# Mainboard.net
KiCad netlist of a schematic drawn in EAGLE
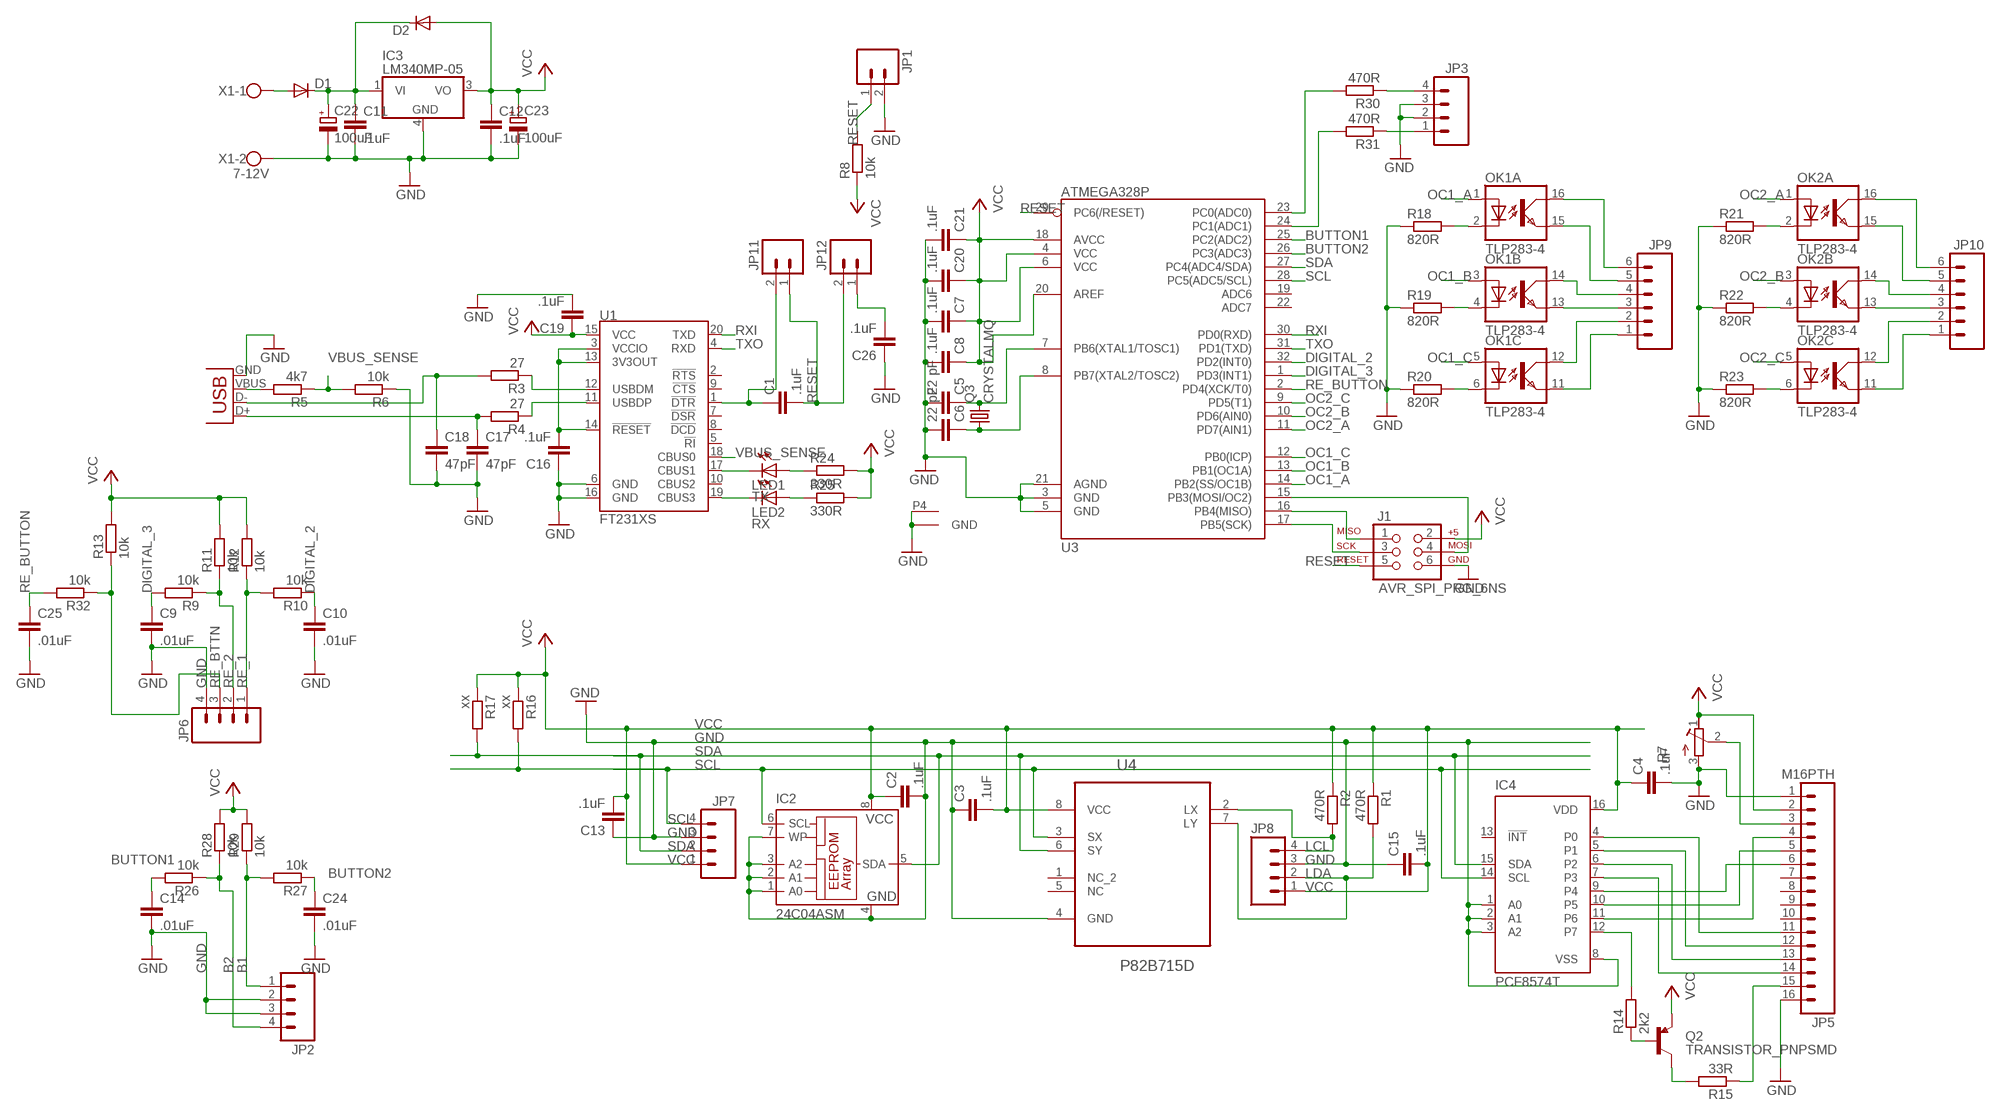
[diagram p0: schematic, sheet 1]

(export (version "E")
  (design (tool "Eeschema 10.0.6"))
  (components
    (comp (ref "C1")
      (value ".1uF")
      (footprint "eagle-import:C0805")
      (fields (field (name "MPN") "2222 370 21104"))
      (libsource (lib "eagle-import") (part "C-EUC0805"))
    )
    (comp (ref "C2")
      (value ".1uF")
      (footprint "eagle-import:C0805")
      (fields (field (name "MPN") "2222 370 21104"))
      (libsource (lib "eagle-import") (part "C-EUC0805"))
    )
    (comp (ref "C3")
      (value ".1uF")
      (footprint "eagle-import:C0805")
      (fields (field (name "MPN") "2222 370 21104"))
      (libsource (lib "eagle-import") (part "C-EUC0805"))
    )
    (comp (ref "C4")
      (value ".1uF")
      (footprint "eagle-import:C0805")
      (fields (field (name "MPN") "2222 370 21104"))
      (libsource (lib "eagle-import") (part "C-EUC0805"))
    )
    (comp (ref "C5")
      (value "22 pF")
      (footprint "eagle-import:C0805")
      (fields (field (name "MPN") "02013A220JAT2A"))
      (libsource (lib "eagle-import") (part "C-EUC0805"))
    )
    (comp (ref "C6")
      (value "22 pF")
      (footprint "eagle-import:C0805")
      (fields (field (name "MPN") "02013A220JAT2A"))
      (libsource (lib "eagle-import") (part "C-EUC0805"))
    )
    (comp (ref "C7")
      (value ".1uF")
      (footprint "eagle-import:C0805")
      (fields (field (name "MPN") "2222 370 21104"))
      (libsource (lib "eagle-import") (part "C-EUC0805"))
    )
    (comp (ref "C8")
      (value ".1uF")
      (footprint "eagle-import:C0805")
      (fields (field (name "MPN") "2222 370 21104"))
      (libsource (lib "eagle-import") (part "C-EUC0805"))
    )
    (comp (ref "C9")
      (value ".01uF")
      (footprint "eagle-import:C0805")
      (fields (field (name "MPN") "B32529C103K"))
      (libsource (lib "eagle-import") (part "C-EUC0805"))
    )
    (comp (ref "C10")
      (value ".01uF")
      (footprint "eagle-import:C0805")
      (fields (field (name "MPN") "B32529C103K"))
      (libsource (lib "eagle-import") (part "C-EUC0805"))
    )
    (comp (ref "C11")
      (value ".1uF")
      (footprint "eagle-import:C0805")
      (fields (field (name "MPN") "2222 370 21104"))
      (libsource (lib "eagle-import") (part "C-EUC0805"))
    )
    (comp (ref "C12")
      (value ".1uF")
      (footprint "eagle-import:C0805")
      (fields (field (name "MPN") "2222 370 21104"))
      (libsource (lib "eagle-import") (part "C-EUC0805"))
    )
    (comp (ref "C13")
      (value ".1uF")
      (footprint "eagle-import:C0805")
      (fields (field (name "MPN") "2222 370 21104"))
      (libsource (lib "eagle-import") (part "C-EUC0805"))
    )
    (comp (ref "C14")
      (value ".01uF")
      (footprint "eagle-import:C0805")
      (fields (field (name "MPN") "B32529C103K"))
      (libsource (lib "eagle-import") (part "C-EUC0805"))
    )
    (comp (ref "C15")
      (value ".1uF")
      (footprint "eagle-import:C0805")
      (fields (field (name "MPN") "2222 370 21104"))
      (libsource (lib "eagle-import") (part "C-EUC0805"))
    )
    (comp (ref "C16")
      (value ".1uF")
      (footprint "eagle-import:C0805")
      (fields (field (name "MPN") "2222 370 21104"))
      (libsource (lib "eagle-import") (part "C-EUC0805"))
    )
    (comp (ref "C17")
      (value "47pF")
      (footprint "eagle-import:C0805")
      (libsource (lib "eagle-import") (part "C-EUC0805"))
    )
    (comp (ref "C18")
      (value "47pF")
      (footprint "eagle-import:C0805")
      (libsource (lib "eagle-import") (part "C-EUC0805"))
    )
    (comp (ref "C19")
      (value ".1uF")
      (footprint "eagle-import:C0805")
      (fields (field (name "MPN") "2222 370 21104"))
      (libsource (lib "eagle-import") (part "C-EUC0805"))
    )
    (comp (ref "C20")
      (value ".1uF")
      (footprint "eagle-import:C0805")
      (fields (field (name "MPN") "2222 370 21104"))
      (libsource (lib "eagle-import") (part "C-EUC0805"))
    )
    (comp (ref "C21")
      (value ".1uF")
      (footprint "eagle-import:C0805")
      (fields (field (name "MPN") "2222 370 21104"))
      (libsource (lib "eagle-import") (part "C-EUC0805"))
    )
    (comp (ref "C22")
      (value "100uF")
      (footprint "eagle-import:PANASONIC_D")
      (libsource (lib "eagle-import") (part "CPOL-EUD"))
    )
    (comp (ref "C23")
      (value "100uF")
      (footprint "eagle-import:PANASONIC_D")
      (libsource (lib "eagle-import") (part "CPOL-EUD"))
    )
    (comp (ref "C24")
      (value ".01uF")
      (footprint "eagle-import:C0805")
      (fields (field (name "MPN") "B32529C103K"))
      (libsource (lib "eagle-import") (part "C-EUC0805"))
    )
    (comp (ref "C25")
      (value ".01uF")
      (footprint "eagle-import:C0805")
      (fields (field (name "MPN") "B32529C103K"))
      (libsource (lib "eagle-import") (part "C-EUC0805"))
    )
    (comp (ref "C26")
      (value ".1uF")
      (footprint "eagle-import:C0805")
      (fields (field (name "MPN") "2222 370 21104"))
      (libsource (lib "eagle-import") (part "C-EUC0805"))
    )
    (comp (ref "D1")
      (value "DIODE-MELF-MLL41")
      (footprint "eagle-import:MELF-MLL41")
      (libsource (lib "eagle-import") (part "DIODE-MELF-MLL41"))
    )
    (comp (ref "D2")
      (value "DIODE-MELF-MLL41")
      (footprint "eagle-import:MELF-MLL41")
      (libsource (lib "eagle-import") (part "DIODE-MELF-MLL41"))
    )
    (comp (ref "IC2")
      (value "24C04ASM")
      (footprint "eagle-import:SO-08M")
      (fields (field (name "MPN") "M24C04-WMN6P"))
      (libsource (lib "eagle-import") (part "24SMC04A"))
    )
    (comp (ref "IC3")
      (value "LM340MP-05")
      (footprint "eagle-import:SOT223")
      (libsource (lib "eagle-import") (part "LM340?-MP05"))
    )
    (comp (ref "IC4")
      (value "PCF8574T")
      (footprint "eagle-import:SO16W")
      (fields (field (name "MPN") "PCF8574T/3,512"))
      (libsource (lib "eagle-import") (part "PCF8574T"))
    )
    (comp (ref "J1")
      (value "AVR_SPI_PRG_6NS")
      (footprint "eagle-import:2X3-NS")
      (libsource (lib "eagle-import") (part "AVR_SPI_PRG_6NS"))
    )
    (comp (ref "JP1")
      (value "M02POLAR")
      (footprint "eagle-import:MOLEX-1X2")
      (libsource (lib "eagle-import") (part "M02POLAR"))
    )
    (comp (ref "JP2")
      (value "M04POLAR")
      (footprint "eagle-import:MOLEX-1X4")
      (libsource (lib "eagle-import") (part "M04POLAR"))
    )
    (comp (ref "JP3")
      (value "M04PTH")
      (footprint "eagle-import:1X04")
      (libsource (lib "eagle-import") (part "M04PTH"))
    )
    (comp (ref "JP4")
      (value "USB-B")
      (footprint "eagle-import:USB-B-PTH")
      (libsource (lib "eagle-import") (part "USBPTH"))
    )
    (comp (ref "JP5")
      (value "M16PTH")
      (footprint "eagle-import:1X16")
      (libsource (lib "eagle-import") (part "M16PTH"))
    )
    (comp (ref "JP6")
      (value "M04POLAR")
      (footprint "eagle-import:MOLEX-1X4")
      (libsource (lib "eagle-import") (part "M04POLAR"))
    )
    (comp (ref "JP7")
      (value "M04POLAR")
      (footprint "eagle-import:MOLEX-1X4")
      (libsource (lib "eagle-import") (part "M04POLAR"))
    )
    (comp (ref "JP8")
      (value "M04POLAR")
      (footprint "eagle-import:MOLEX-1X4")
      (libsource (lib "eagle-import") (part "M04POLAR"))
    )
    (comp (ref "JP9")
      (value "M06POLAR")
      (footprint "eagle-import:MOLEX-1X6")
      (libsource (lib "eagle-import") (part "M06POLAR"))
    )
    (comp (ref "JP10")
      (value "M06POLAR")
      (footprint "eagle-import:MOLEX-1X6")
      (libsource (lib "eagle-import") (part "M06POLAR"))
    )
    (comp (ref "JP11")
      (value "M02PTH")
      (footprint "eagle-import:1X02")
      (libsource (lib "eagle-import") (part "M02PTH"))
    )
    (comp (ref "JP12")
      (value "M02PTH")
      (footprint "eagle-import:1X02")
      (libsource (lib "eagle-import") (part "M02PTH"))
    )
    (comp (ref "LED1")
      (value "TX")
      (footprint "eagle-import:CHIPLED_0805")
      (libsource (lib "eagle-import") (part "LEDCHIPLED_0805"))
    )
    (comp (ref "LED2")
      (value "RX")
      (footprint "eagle-import:CHIPLED_0805")
      (libsource (lib "eagle-import") (part "LEDCHIPLED_0805"))
    )
    (comp (ref "OK1")
      (value "TLP283-4")
      (footprint "eagle-import:MINI-FLAT-16")
      (libsource (lib "eagle-import") (part "TLP283-4"))
    )
    (comp (ref "OK2")
      (value "TLP283-4")
      (footprint "eagle-import:MINI-FLAT-16")
      (libsource (lib "eagle-import") (part "TLP283-4"))
    )
    (comp (ref "Q2")
      (value "TRANSISTOR_PNPSMD")
      (footprint "eagle-import:SOT23-3")
      (libsource (lib "eagle-import") (part "TRANSISTOR_PNPSMD"))
    )
    (comp (ref "Q3")
      (value "CRYSTALMQ")
      (footprint "eagle-import:MQ")
      (libsource (lib "eagle-import") (part "CRYSTALMQ"))
    )
    (comp (ref "R1")
      (value "470R")
      (footprint "eagle-import:R0805")
      (libsource (lib "eagle-import") (part "R-EU_R0805"))
    )
    (comp (ref "R2")
      (value "470R")
      (footprint "eagle-import:R0805")
      (libsource (lib "eagle-import") (part "R-EU_R0805"))
    )
    (comp (ref "R3")
      (value "27")
      (footprint "eagle-import:R0805")
      (libsource (lib "eagle-import") (part "R-EU_R0805"))
    )
    (comp (ref "R4")
      (value "27")
      (footprint "eagle-import:R0805")
      (libsource (lib "eagle-import") (part "R-EU_R0805"))
    )
    (comp (ref "R5")
      (value "4k7")
      (footprint "eagle-import:R0805")
      (libsource (lib "eagle-import") (part "R-EU_R0805"))
    )
    (comp (ref "R6")
      (value "10k")
      (footprint "eagle-import:R0805")
      (fields (field (name "MF") "VISHAY/SPECTRO") (field (name "MPN") "043P103"))
      (libsource (lib "eagle-import") (part "R-EU_R0805"))
    )
    (comp (ref "R7")
      (value "R-TRIMM3314G")
      (footprint "eagle-import:RTRIM3314G")
      (libsource (lib "eagle-import") (part "R-TRIMM3314G"))
    )
    (comp (ref "R8")
      (value "10k")
      (footprint "eagle-import:R0805")
      (fields (field (name "MF") "VISHAY/SPECTRO") (field (name "MPN") "043P103"))
      (libsource (lib "eagle-import") (part "R-EU_R0805"))
    )
    (comp (ref "R9")
      (value "10k")
      (footprint "eagle-import:R0805")
      (fields (field (name "MF") "VISHAY/SPECTRO") (field (name "MPN") "043P103"))
      (libsource (lib "eagle-import") (part "R-EU_R0805"))
    )
    (comp (ref "R10")
      (value "10k")
      (footprint "eagle-import:R0805")
      (fields (field (name "MF") "VISHAY/SPECTRO") (field (name "MPN") "043P103"))
      (libsource (lib "eagle-import") (part "R-EU_R0805"))
    )
    (comp (ref "R11")
      (value "10k")
      (footprint "eagle-import:R0805")
      (fields (field (name "MF") "VISHAY/SPECTRO") (field (name "MPN") "043P103"))
      (libsource (lib "eagle-import") (part "R-EU_R0805"))
    )
    (comp (ref "R12")
      (value "10k")
      (footprint "eagle-import:R0805")
      (fields (field (name "MF") "VISHAY/SPECTRO") (field (name "MPN") "043P103"))
      (libsource (lib "eagle-import") (part "R-EU_R0805"))
    )
    (comp (ref "R13")
      (value "10k")
      (footprint "eagle-import:R0805")
      (fields (field (name "MF") "VISHAY/SPECTRO") (field (name "MPN") "043P103"))
      (libsource (lib "eagle-import") (part "R-EU_R0805"))
    )
    (comp (ref "R14")
      (value "2k2")
      (footprint "eagle-import:R0805")
      (fields (field (name "MF") "VISHAY/SPECTRO") (field (name "MPN") "043P103"))
      (libsource (lib "eagle-import") (part "R-EU_R0805"))
    )
    (comp (ref "R15")
      (value "33R")
      (footprint "eagle-import:R0805")
      (fields (field (name "MF") "VISHAY/SPECTRO") (field (name "MPN") "043P103"))
      (libsource (lib "eagle-import") (part "R-EU_R0805"))
    )
    (comp (ref "R16")
      (value "xx")
      (footprint "eagle-import:R0805")
      (libsource (lib "eagle-import") (part "R-EU_R0805"))
    )
    (comp (ref "R17")
      (value "xx")
      (footprint "eagle-import:R0805")
      (libsource (lib "eagle-import") (part "R-EU_R0805"))
    )
    (comp (ref "R18")
      (value "820R")
      (footprint "eagle-import:R0805")
      (libsource (lib "eagle-import") (part "R-EU_R0805"))
    )
    (comp (ref "R19")
      (value "820R")
      (footprint "eagle-import:R0805")
      (libsource (lib "eagle-import") (part "R-EU_R0805"))
    )
    (comp (ref "R20")
      (value "820R")
      (footprint "eagle-import:R0805")
      (libsource (lib "eagle-import") (part "R-EU_R0805"))
    )
    (comp (ref "R21")
      (value "820R")
      (footprint "eagle-import:R0805")
      (libsource (lib "eagle-import") (part "R-EU_R0805"))
    )
    (comp (ref "R22")
      (value "820R")
      (footprint "eagle-import:R0805")
      (libsource (lib "eagle-import") (part "R-EU_R0805"))
    )
    (comp (ref "R23")
      (value "820R")
      (footprint "eagle-import:R0805")
      (libsource (lib "eagle-import") (part "R-EU_R0805"))
    )
    (comp (ref "R24")
      (value "330R")
      (footprint "eagle-import:R0805")
      (libsource (lib "eagle-import") (part "R-EU_R0805"))
    )
    (comp (ref "R25")
      (value "330R")
      (footprint "eagle-import:R0805")
      (libsource (lib "eagle-import") (part "R-EU_R0805"))
    )
    (comp (ref "R26")
      (value "10k")
      (footprint "eagle-import:R0805")
      (fields (field (name "MF") "VISHAY/SPECTRO") (field (name "MPN") "043P103"))
      (libsource (lib "eagle-import") (part "R-EU_R0805"))
    )
    (comp (ref "R27")
      (value "10k")
      (footprint "eagle-import:R0805")
      (fields (field (name "MF") "VISHAY/SPECTRO") (field (name "MPN") "043P103"))
      (libsource (lib "eagle-import") (part "R-EU_R0805"))
    )
    (comp (ref "R28")
      (value "10k")
      (footprint "eagle-import:R0805")
      (fields (field (name "MF") "VISHAY/SPECTRO") (field (name "MPN") "043P103"))
      (libsource (lib "eagle-import") (part "R-EU_R0805"))
    )
    (comp (ref "R29")
      (value "10k")
      (footprint "eagle-import:R0805")
      (fields (field (name "MF") "VISHAY/SPECTRO") (field (name "MPN") "043P103"))
      (libsource (lib "eagle-import") (part "R-EU_R0805"))
    )
    (comp (ref "R30")
      (value "470R")
      (footprint "eagle-import:R0805")
      (fields (field (name "MF") "VISHAY/SPECTRO") (field (name "MPN") "043P103"))
      (libsource (lib "eagle-import") (part "R-EU_R0805"))
    )
    (comp (ref "R31")
      (value "470R")
      (footprint "eagle-import:R0805")
      (fields (field (name "MF") "VISHAY/SPECTRO") (field (name "MPN") "043P103"))
      (libsource (lib "eagle-import") (part "R-EU_R0805"))
    )
    (comp (ref "R32")
      (value "10k")
      (footprint "eagle-import:R0805")
      (fields (field (name "MF") "VISHAY/SPECTRO") (field (name "MPN") "043P103"))
      (libsource (lib "eagle-import") (part "R-EU_R0805"))
    )
    (comp (ref "U1")
      (value "FT231XS")
      (footprint "eagle-import:SSOP20_L")
      (libsource (lib "eagle-import") (part "FT231XS"))
    )
    (comp (ref "U3")
      (value "ATMEGA328P")
      (footprint "eagle-import:TQFP32-08")
      (libsource (lib "eagle-import") (part "ATMEGA328_SMT"))
    )
    (comp (ref "U4")
      (value "P82B715D")
      (footprint "eagle-import:SOIC127P600X175-8N")
      (libsource (lib "eagle-import") (part "P82B715D"))
    )
    (comp (ref "X1")
      (value "7-12V")
      (footprint "eagle-import:W237-102")
      (fields (field (name "MPN") "237-102") (field (name "OC_NEWARK") "unknown"))
      (libsource (lib "eagle-import") (part "W237-102"))
    )
  )
  (nets
    (net (code "1") (name "/B1") (class "Default")
      (node (ref "JP2") (pin "1") (pinfunction "1_1") (pintype "passive"))
      (node (ref "R27") (pin "2") (pinfunction "2_2") (pintype "passive"))
      (node (ref "R29") (pin "1") (pinfunction "1_1") (pintype "passive"))
    )
    (net (code "2") (name "/B2") (class "Default")
      (node (ref "JP2") (pin "4") (pinfunction "4_4") (pintype "passive"))
      (node (ref "R26") (pin "1") (pinfunction "1_1") (pintype "passive"))
      (node (ref "R28") (pin "1") (pinfunction "1_1") (pintype "passive"))
    )
    (net (code "3") (name "/BUTTON1") (class "Default")
      (node (ref "C14") (pin "1") (pinfunction "1_1") (pintype "passive"))
      (node (ref "R26") (pin "2") (pinfunction "2_2") (pintype "passive"))
      (node (ref "U3") (pin "25") (pinfunction "PC2(ADC2)_25") (pintype "bidirectional"))
    )
    (net (code "4") (name "/BUTTON2") (class "Default")
      (node (ref "C24") (pin "1") (pinfunction "1_1") (pintype "passive"))
      (node (ref "R27") (pin "1") (pinfunction "1_1") (pintype "passive"))
      (node (ref "U3") (pin "26") (pinfunction "PC3(ADC3)_26") (pintype "bidirectional"))
    )
    (net (code "5") (name "/DIGITAL_2") (class "Default")
      (node (ref "C10") (pin "1") (pinfunction "1_1") (pintype "passive"))
      (node (ref "R10") (pin "1") (pinfunction "1_1") (pintype "passive"))
      (node (ref "U3") (pin "32") (pinfunction "PD2(INT0)_32") (pintype "bidirectional"))
    )
    (net (code "6") (name "/DIGITAL_3") (class "Default")
      (node (ref "C9") (pin "1") (pinfunction "1_1") (pintype "passive"))
      (node (ref "R9") (pin "2") (pinfunction "2_2") (pintype "passive"))
      (node (ref "U3") (pin "1") (pinfunction "PD3(INT1)_1") (pintype "bidirectional"))
    )
    (net (code "7") (name "/LCL") (class "Default")
      (node (ref "JP8") (pin "4") (pinfunction "4_4") (pintype "passive"))
      (node (ref "R2") (pin "2") (pinfunction "2_2") (pintype "passive"))
      (node (ref "U4") (pin "2") (pinfunction "LX_2") (pintype "output"))
    )
    (net (code "8") (name "/LDA") (class "Default")
      (node (ref "JP8") (pin "2") (pinfunction "2_2") (pintype "passive"))
      (node (ref "R1") (pin "2") (pinfunction "2_2") (pintype "passive"))
      (node (ref "U4") (pin "7") (pinfunction "LY_7") (pintype "output"))
    )
    (net (code "9") (name "/OC1_A") (class "Default")
      (node (ref "OK1") (pin "1") (pinfunction "A_1") (pintype "passive"))
      (node (ref "U3") (pin "14") (pinfunction "PB2(SS/OC1B)_14") (pintype "bidirectional"))
    )
    (net (code "10") (name "/OC1_B") (class "Default")
      (node (ref "OK1") (pin "3") (pinfunction "A_3") (pintype "passive"))
      (node (ref "U3") (pin "13") (pinfunction "PB1(OC1A)_13") (pintype "bidirectional"))
    )
    (net (code "11") (name "/OC1_C") (class "Default")
      (node (ref "OK1") (pin "5") (pinfunction "A_5") (pintype "passive"))
      (node (ref "U3") (pin "12") (pinfunction "PB0(ICP)_12") (pintype "bidirectional"))
    )
    (net (code "12") (name "/OC2_A") (class "Default")
      (node (ref "OK2") (pin "1") (pinfunction "A_1") (pintype "passive"))
      (node (ref "U3") (pin "11") (pinfunction "PD7(AIN1)_11") (pintype "bidirectional"))
    )
    (net (code "13") (name "/OC2_B") (class "Default")
      (node (ref "OK2") (pin "3") (pinfunction "A_3") (pintype "passive"))
      (node (ref "U3") (pin "10") (pinfunction "PD6(AIN0)_10") (pintype "bidirectional"))
    )
    (net (code "14") (name "/OC2_C") (class "Default")
      (node (ref "OK2") (pin "5") (pinfunction "A_5") (pintype "passive"))
      (node (ref "U3") (pin "9") (pinfunction "PD5(T1)_9") (pintype "bidirectional"))
    )
    (net (code "15") (name "/RESET") (class "Default")
      (node (ref "C1") (pin "2") (pinfunction "2_2") (pintype "passive"))
      (node (ref "J1") (pin "5") (pinfunction "5_5") (pintype "passive"))
      (node (ref "JP1") (pin "1") (pinfunction "1_1") (pintype "passive"))
      (node (ref "JP11") (pin "1") (pinfunction "1_1") (pintype "passive"))
      (node (ref "JP12") (pin "2") (pinfunction "2_2") (pintype "passive"))
      (node (ref "R8") (pin "2") (pinfunction "2_2") (pintype "passive"))
      (node (ref "U3") (pin "29") (pinfunction "PC6(/RESET)_29") (pintype "bidirectional"))
    )
    (net (code "16") (name "/RE_1") (class "Default")
      (node (ref "JP6") (pin "1") (pinfunction "1_1") (pintype "passive"))
      (node (ref "R10") (pin "2") (pinfunction "2_2") (pintype "passive"))
      (node (ref "R12") (pin "1") (pinfunction "1_1") (pintype "passive"))
    )
    (net (code "17") (name "/RE_2") (class "Default")
      (node (ref "JP6") (pin "2") (pinfunction "2_2") (pintype "passive"))
      (node (ref "R11") (pin "1") (pinfunction "1_1") (pintype "passive"))
      (node (ref "R9") (pin "1") (pinfunction "1_1") (pintype "passive"))
    )
    (net (code "18") (name "/RE_BTTN") (class "Default")
      (node (ref "JP6") (pin "3") (pinfunction "3_3") (pintype "passive"))
      (node (ref "R13") (pin "1") (pinfunction "1_1") (pintype "passive"))
      (node (ref "R32") (pin "1") (pinfunction "1_1") (pintype "passive"))
    )
    (net (code "19") (name "/RE_BUTTON") (class "Default")
      (node (ref "C25") (pin "1") (pinfunction "1_1") (pintype "passive"))
      (node (ref "R32") (pin "2") (pinfunction "2_2") (pintype "passive"))
      (node (ref "U3") (pin "2") (pinfunction "PD4(XCK/T0)_2") (pintype "bidirectional"))
    )
    (net (code "20") (name "/RXI") (class "Default")
      (node (ref "U1") (pin "20") (pinfunction "TXD_20") (pintype "bidirectional"))
      (node (ref "U3") (pin "30") (pinfunction "PD0(RXD)_30") (pintype "bidirectional"))
    )
    (net (code "21") (name "/SCL") (class "Default")
      (node (ref "IC2") (pin "6") (pinfunction "SCL_6") (pintype "input"))
      (node (ref "IC4") (pin "14") (pinfunction "SCL_14") (pintype "input"))
      (node (ref "JP7") (pin "4") (pinfunction "4_4") (pintype "passive"))
      (node (ref "R16") (pin "2") (pinfunction "2_2") (pintype "passive"))
      (node (ref "U3") (pin "28") (pinfunction "PC5(ADC5/SCL)_28") (pintype "bidirectional"))
      (node (ref "U4") (pin "3") (pinfunction "SX_3") (pintype "input"))
    )
    (net (code "22") (name "/SDA") (class "Default")
      (node (ref "IC2") (pin "5") (pinfunction "SDA_5") (pintype "bidirectional"))
      (node (ref "IC4") (pin "15") (pinfunction "SDA_15") (pintype "bidirectional"))
      (node (ref "JP7") (pin "2") (pinfunction "2_2") (pintype "passive"))
      (node (ref "R17") (pin "2") (pinfunction "2_2") (pintype "passive"))
      (node (ref "U3") (pin "27") (pinfunction "PC4(ADC4/SDA)_27") (pintype "bidirectional"))
      (node (ref "U4") (pin "6") (pinfunction "SY_6") (pintype "input"))
    )
    (net (code "23") (name "/TXO") (class "Default")
      (node (ref "U1") (pin "4") (pinfunction "RXD_4") (pintype "bidirectional"))
      (node (ref "U3") (pin "31") (pinfunction "PD1(TXD)_31") (pintype "bidirectional"))
    )
    (net (code "24") (name "/VBUS_SENSE") (class "Default")
      (node (ref "R5") (pin "1") (pinfunction "1_1") (pintype "passive"))
      (node (ref "R6") (pin "2") (pinfunction "2_2") (pintype "passive"))
      (node (ref "U1") (pin "18") (pinfunction "CBUS0_18") (pintype "bidirectional"))
    )
    (net (code "25") (name "GND") (class "Default")
      (node (ref "C10") (pin "2") (pinfunction "2_2") (pintype "passive"))
      (node (ref "C11") (pin "2") (pinfunction "2_2") (pintype "passive"))
      (node (ref "C12") (pin "2") (pinfunction "2_2") (pintype "passive"))
      (node (ref "C13") (pin "1") (pinfunction "1_1") (pintype "passive"))
      (node (ref "C14") (pin "2") (pinfunction "2_2") (pintype "passive"))
      (node (ref "C15") (pin "1") (pinfunction "1_1") (pintype "passive"))
      (node (ref "C16") (pin "1") (pinfunction "1_1") (pintype "passive"))
      (node (ref "C17") (pin "2") (pinfunction "2_2") (pintype "passive"))
      (node (ref "C18") (pin "2") (pinfunction "2_2") (pintype "passive"))
      (node (ref "C19") (pin "2") (pinfunction "2_2") (pintype "passive"))
      (node (ref "C2") (pin "2") (pinfunction "2_2") (pintype "passive"))
      (node (ref "C20") (pin "2") (pinfunction "2_2") (pintype "passive"))
      (node (ref "C21") (pin "2") (pinfunction "2_2") (pintype "passive"))
      (node (ref "C22") (pin "-") (pinfunction "-_-") (pintype "passive"))
      (node (ref "C23") (pin "-") (pinfunction "-_-") (pintype "passive"))
      (node (ref "C24") (pin "2") (pinfunction "2_2") (pintype "passive"))
      (node (ref "C25") (pin "2") (pinfunction "2_2") (pintype "passive"))
      (node (ref "C26") (pin "1") (pinfunction "1_1") (pintype "passive"))
      (node (ref "C3") (pin "1") (pinfunction "1_1") (pintype "passive"))
      (node (ref "C4") (pin "2") (pinfunction "2_2") (pintype "passive"))
      (node (ref "C5") (pin "2") (pinfunction "2_2") (pintype "passive"))
      (node (ref "C6") (pin "2") (pinfunction "2_2") (pintype "passive"))
      (node (ref "C7") (pin "2") (pinfunction "2_2") (pintype "passive"))
      (node (ref "C8") (pin "2") (pinfunction "2_2") (pintype "passive"))
      (node (ref "C9") (pin "2") (pinfunction "2_2") (pintype "passive"))
      (node (ref "IC2") (pin "1") (pinfunction "A0_1") (pintype "input"))
      (node (ref "IC2") (pin "2") (pinfunction "A1_2") (pintype "input"))
      (node (ref "IC2") (pin "3") (pinfunction "A2_3") (pintype "input"))
      (node (ref "IC2") (pin "4") (pinfunction "GND_4") (pintype "power_in"))
      (node (ref "IC2") (pin "7") (pinfunction "WP_7") (pintype "input"))
      (node (ref "IC3") (pin "4") (pinfunction "GND_4") (pintype "passive"))
      (node (ref "IC4") (pin "1") (pinfunction "A0_1") (pintype "input"))
      (node (ref "IC4") (pin "2") (pinfunction "A1_2") (pintype "input"))
      (node (ref "IC4") (pin "3") (pinfunction "A2_3") (pintype "input"))
      (node (ref "IC4") (pin "8") (pinfunction "VSS_8") (pintype "power_in"))
      (node (ref "J1") (pin "6") (pinfunction "6_6") (pintype "passive"))
      (node (ref "JP1") (pin "2") (pinfunction "2_2") (pintype "passive"))
      (node (ref "JP2") (pin "2") (pinfunction "2_2") (pintype "passive"))
      (node (ref "JP2") (pin "3") (pinfunction "3_3") (pintype "passive"))
      (node (ref "JP3") (pin "2") (pinfunction "2_2") (pintype "passive"))
      (node (ref "JP3") (pin "3") (pinfunction "3_3") (pintype "passive"))
      (node (ref "JP4") (pin "GND") (pinfunction "GND_GND") (pintype "bidirectional"))
      (node (ref "JP5") (pin "1") (pinfunction "1_1") (pintype "passive"))
      (node (ref "JP5") (pin "16") (pinfunction "16_16") (pintype "passive"))
      (node (ref "JP6") (pin "4") (pinfunction "4_4") (pintype "passive"))
      (node (ref "JP7") (pin "3") (pinfunction "3_3") (pintype "passive"))
      (node (ref "JP8") (pin "3") (pinfunction "3_3") (pintype "passive"))
      (node (ref "Q3") (pin "P2") (pinfunction "GND_P2") (pintype "bidirectional"))
      (node (ref "Q3") (pin "P4") (pinfunction "GND1_P4") (pintype "bidirectional"))
      (node (ref "R18") (pin "1") (pinfunction "1_1") (pintype "passive"))
      (node (ref "R19") (pin "1") (pinfunction "1_1") (pintype "passive"))
      (node (ref "R20") (pin "1") (pinfunction "1_1") (pintype "passive"))
      (node (ref "R21") (pin "1") (pinfunction "1_1") (pintype "passive"))
      (node (ref "R22") (pin "1") (pinfunction "1_1") (pintype "passive"))
      (node (ref "R23") (pin "1") (pinfunction "1_1") (pintype "passive"))
      (node (ref "R6") (pin "1") (pinfunction "1_1") (pintype "passive"))
      (node (ref "R7") (pin "3") (pinfunction "A_3") (pintype "passive"))
      (node (ref "U1") (pin "16") (pinfunction "GND_16") (pintype "bidirectional"))
      (node (ref "U1") (pin "6") (pinfunction "GND_6") (pintype "bidirectional"))
      (node (ref "U3") (pin "21") (pinfunction "AGND_21") (pintype "bidirectional"))
      (node (ref "U3") (pin "3") (pinfunction "GND_3") (pintype "bidirectional"))
      (node (ref "U3") (pin "5") (pinfunction "GND_5") (pintype "bidirectional"))
      (node (ref "U4") (pin "4") (pinfunction "GND_4") (pintype "passive"))
      (node (ref "X1") (pin "2") (pinfunction "KL_2") (pintype "passive"))
    )
    (net (code "26") (name "Net-(C17-Pad1)") (class "Default")
      (node (ref "C17") (pin "1") (pinfunction "1_1") (pintype "passive"))
      (node (ref "JP4") (pin "D+") (pinfunction "D+_D+") (pintype "bidirectional"))
      (node (ref "R4") (pin "2") (pinfunction "2_2") (pintype "passive"))
    )
    (net (code "27") (name "Net-(C18-Pad1)") (class "Default")
      (node (ref "C18") (pin "1") (pinfunction "1_1") (pintype "passive"))
      (node (ref "JP4") (pin "D-") (pinfunction "D-_D-") (pintype "bidirectional"))
      (node (ref "R3") (pin "2") (pinfunction "2_2") (pintype "passive"))
    )
    (net (code "28") (name "Net-(C26-Pad2)") (class "Default")
      (node (ref "C26") (pin "2") (pinfunction "2_2") (pintype "passive"))
      (node (ref "JP12") (pin "1") (pinfunction "1_1") (pintype "passive"))
    )
    (net (code "29") (name "Net-(IC3-VI)") (class "Default")
      (node (ref "C11") (pin "1") (pinfunction "1_1") (pintype "passive"))
      (node (ref "C22") (pin "+") (pinfunction "+_+") (pintype "passive"))
      (node (ref "D1") (pin "C") (pinfunction "C_C") (pintype "passive"))
      (node (ref "D2") (pin "C") (pinfunction "C_C") (pintype "passive"))
      (node (ref "IC3") (pin "1") (pinfunction "VI_1") (pintype "input"))
    )
    (net (code "30") (name "Net-(IC4-P0)") (class "Default")
      (node (ref "IC4") (pin "4") (pinfunction "P0_4") (pintype "bidirectional"))
      (node (ref "JP5") (pin "11") (pinfunction "11_11") (pintype "passive"))
    )
    (net (code "31") (name "Net-(IC4-P1)") (class "Default")
      (node (ref "IC4") (pin "5") (pinfunction "P1_5") (pintype "bidirectional"))
      (node (ref "JP5") (pin "12") (pinfunction "12_12") (pintype "passive"))
    )
    (net (code "32") (name "Net-(IC4-P2)") (class "Default")
      (node (ref "IC4") (pin "6") (pinfunction "P2_6") (pintype "bidirectional"))
      (node (ref "JP5") (pin "13") (pinfunction "13_13") (pintype "passive"))
    )
    (net (code "33") (name "Net-(IC4-P3)") (class "Default")
      (node (ref "IC4") (pin "7") (pinfunction "P3_7") (pintype "bidirectional"))
      (node (ref "JP5") (pin "14") (pinfunction "14_14") (pintype "passive"))
    )
    (net (code "34") (name "Net-(IC4-P4)") (class "Default")
      (node (ref "IC4") (pin "9") (pinfunction "P4_9") (pintype "bidirectional"))
      (node (ref "JP5") (pin "6") (pinfunction "6_6") (pintype "passive"))
    )
    (net (code "35") (name "Net-(IC4-P5)") (class "Default")
      (node (ref "IC4") (pin "10") (pinfunction "P5_10") (pintype "bidirectional"))
      (node (ref "JP5") (pin "5") (pinfunction "5_5") (pintype "passive"))
    )
    (net (code "36") (name "Net-(IC4-P6)") (class "Default")
      (node (ref "IC4") (pin "11") (pinfunction "P6_11") (pintype "bidirectional"))
      (node (ref "JP5") (pin "4") (pinfunction "4_4") (pintype "passive"))
    )
    (net (code "37") (name "Net-(IC4-P7)") (class "Default")
      (node (ref "IC4") (pin "12") (pinfunction "P7_12") (pintype "bidirectional"))
      (node (ref "R14") (pin "2") (pinfunction "2_2") (pintype "passive"))
    )
    (net (code "38") (name "Net-(JP3-Pad1)") (class "Default")
      (node (ref "JP3") (pin "1") (pinfunction "1_1") (pintype "passive"))
      (node (ref "R31") (pin "1") (pinfunction "1_1") (pintype "passive"))
    )
    (net (code "39") (name "Net-(JP3-Pad4)") (class "Default")
      (node (ref "JP3") (pin "4") (pinfunction "4_4") (pintype "passive"))
      (node (ref "R30") (pin "1") (pinfunction "1_1") (pintype "passive"))
    )
    (net (code "40") (name "Net-(JP4-PadVBUS)") (class "Default")
      (node (ref "JP4") (pin "VBUS") (pinfunction "VBUS_VBUS") (pintype "bidirectional"))
      (node (ref "R5") (pin "2") (pinfunction "2_2") (pintype "passive"))
    )
    (net (code "41") (name "Net-(JP5-Pad15)") (class "Default")
      (node (ref "JP5") (pin "15") (pinfunction "15_15") (pintype "passive"))
      (node (ref "R15") (pin "1") (pinfunction "1_1") (pintype "passive"))
    )
    (net (code "42") (name "Net-(LED1-PadA)") (class "Default")
      (node (ref "LED1") (pin "A") (pinfunction "A_A") (pintype "passive"))
      (node (ref "R24") (pin "1") (pinfunction "1_1") (pintype "passive"))
    )
    (net (code "43") (name "Net-(LED2-PadA)") (class "Default")
      (node (ref "LED2") (pin "A") (pinfunction "A_A") (pintype "passive"))
      (node (ref "R25") (pin "1") (pinfunction "1_1") (pintype "passive"))
    )
    (net (code "44") (name "Net-(OK1A-C)") (class "Default")
      (node (ref "OK1") (pin "2") (pinfunction "C_2") (pintype "passive"))
      (node (ref "R18") (pin "2") (pinfunction "2_2") (pintype "passive"))
    )
    (net (code "45") (name "Net-(OK1A-COL)") (class "Default")
      (node (ref "JP9") (pin "6") (pinfunction "6_6") (pintype "passive"))
      (node (ref "OK1") (pin "16") (pinfunction "COL_16") (pintype "passive"))
    )
    (net (code "46") (name "Net-(OK1A-EMIT)") (class "Default")
      (node (ref "JP9") (pin "5") (pinfunction "5_5") (pintype "passive"))
      (node (ref "OK1") (pin "15") (pinfunction "EMIT_15") (pintype "passive"))
    )
    (net (code "47") (name "Net-(OK1B-C)") (class "Default")
      (node (ref "OK1") (pin "4") (pinfunction "C_4") (pintype "passive"))
      (node (ref "R19") (pin "2") (pinfunction "2_2") (pintype "passive"))
    )
    (net (code "48") (name "Net-(OK1B-COL)") (class "Default")
      (node (ref "JP9") (pin "4") (pinfunction "4_4") (pintype "passive"))
      (node (ref "OK1") (pin "14") (pinfunction "COL_14") (pintype "passive"))
    )
    (net (code "49") (name "Net-(OK1B-EMIT)") (class "Default")
      (node (ref "JP9") (pin "3") (pinfunction "3_3") (pintype "passive"))
      (node (ref "OK1") (pin "13") (pinfunction "EMIT_13") (pintype "passive"))
    )
    (net (code "50") (name "Net-(OK1C-C)") (class "Default")
      (node (ref "OK1") (pin "6") (pinfunction "C_6") (pintype "passive"))
      (node (ref "R20") (pin "2") (pinfunction "2_2") (pintype "passive"))
    )
    (net (code "51") (name "Net-(OK1C-COL)") (class "Default")
      (node (ref "JP9") (pin "2") (pinfunction "2_2") (pintype "passive"))
      (node (ref "OK1") (pin "12") (pinfunction "COL_12") (pintype "passive"))
    )
    (net (code "52") (name "Net-(OK1C-EMIT)") (class "Default")
      (node (ref "JP9") (pin "1") (pinfunction "1_1") (pintype "passive"))
      (node (ref "OK1") (pin "11") (pinfunction "EMIT_11") (pintype "passive"))
    )
    (net (code "53") (name "Net-(OK2A-C)") (class "Default")
      (node (ref "OK2") (pin "2") (pinfunction "C_2") (pintype "passive"))
      (node (ref "R21") (pin "2") (pinfunction "2_2") (pintype "passive"))
    )
    (net (code "54") (name "Net-(OK2A-COL)") (class "Default")
      (node (ref "JP10") (pin "6") (pinfunction "6_6") (pintype "passive"))
      (node (ref "OK2") (pin "16") (pinfunction "COL_16") (pintype "passive"))
    )
    (net (code "55") (name "Net-(OK2A-EMIT)") (class "Default")
      (node (ref "JP10") (pin "5") (pinfunction "5_5") (pintype "passive"))
      (node (ref "OK2") (pin "15") (pinfunction "EMIT_15") (pintype "passive"))
    )
    (net (code "56") (name "Net-(OK2B-C)") (class "Default")
      (node (ref "OK2") (pin "4") (pinfunction "C_4") (pintype "passive"))
      (node (ref "R22") (pin "2") (pinfunction "2_2") (pintype "passive"))
    )
    (net (code "57") (name "Net-(OK2B-COL)") (class "Default")
      (node (ref "JP10") (pin "4") (pinfunction "4_4") (pintype "passive"))
      (node (ref "OK2") (pin "14") (pinfunction "COL_14") (pintype "passive"))
    )
    (net (code "58") (name "Net-(OK2B-EMIT)") (class "Default")
      (node (ref "JP10") (pin "3") (pinfunction "3_3") (pintype "passive"))
      (node (ref "OK2") (pin "13") (pinfunction "EMIT_13") (pintype "passive"))
    )
    (net (code "59") (name "Net-(OK2C-C)") (class "Default")
      (node (ref "OK2") (pin "6") (pinfunction "C_6") (pintype "passive"))
      (node (ref "R23") (pin "2") (pinfunction "2_2") (pintype "passive"))
    )
    (net (code "60") (name "Net-(OK2C-COL)") (class "Default")
      (node (ref "JP10") (pin "2") (pinfunction "2_2") (pintype "passive"))
      (node (ref "OK2") (pin "12") (pinfunction "COL_12") (pintype "passive"))
    )
    (net (code "61") (name "Net-(OK2C-EMIT)") (class "Default")
      (node (ref "JP10") (pin "1") (pinfunction "1_1") (pintype "passive"))
      (node (ref "OK2") (pin "11") (pinfunction "EMIT_11") (pintype "passive"))
    )
    (net (code "62") (name "Net-(Q2-B)") (class "Default")
      (node (ref "Q2") (pin "1") (pinfunction "B_1") (pintype "passive"))
      (node (ref "R14") (pin "1") (pinfunction "1_1") (pintype "passive"))
    )
    (net (code "63") (name "Net-(Q2-C)") (class "Default")
      (node (ref "Q2") (pin "3") (pinfunction "C_3") (pintype "passive"))
      (node (ref "R15") (pin "2") (pinfunction "2_2") (pintype "passive"))
    )
    (net (code "64") (name "Net-(Q3A-1)") (class "Default")
      (node (ref "C6") (pin "1") (pinfunction "1_1") (pintype "passive"))
      (node (ref "Q3") (pin "P1") (pinfunction "1_P1") (pintype "passive"))
      (node (ref "U3") (pin "8") (pinfunction "PB7(XTAL2/TOSC2)_8") (pintype "bidirectional"))
    )
    (net (code "65") (name "Net-(Q3A-2)") (class "Default")
      (node (ref "C5") (pin "1") (pinfunction "1_1") (pintype "passive"))
      (node (ref "Q3") (pin "P3") (pinfunction "2_P3") (pintype "passive"))
      (node (ref "U3") (pin "7") (pinfunction "PB6(XTAL1/TOSC1)_7") (pintype "bidirectional"))
    )
    (net (code "66") (name "Net-(R7-S)") (class "Default")
      (node (ref "JP5") (pin "3") (pinfunction "3_3") (pintype "passive"))
      (node (ref "R7") (pin "2") (pinfunction "S_2") (pintype "passive"))
    )
    (net (code "67") (name "Net-(U1-3V3OUT)") (class "Default")
      (node (ref "C16") (pin "2") (pinfunction "2_2") (pintype "passive"))
      (node (ref "U1") (pin "13") (pinfunction "3V3OUT_13") (pintype "bidirectional"))
      (node (ref "U1") (pin "14") (pinfunction "~{RESET}_14") (pintype "bidirectional"))
      (node (ref "U1") (pin "3") (pinfunction "VCCIO_3") (pintype "bidirectional"))
    )
    (net (code "68") (name "Net-(U1-CBUS1)") (class "Default")
      (node (ref "LED1") (pin "C") (pinfunction "C_C") (pintype "passive"))
      (node (ref "U1") (pin "17") (pinfunction "CBUS1_17") (pintype "bidirectional"))
    )
    (net (code "69") (name "Net-(U1-CBUS3)") (class "Default")
      (node (ref "LED2") (pin "C") (pinfunction "C_C") (pintype "passive"))
      (node (ref "U1") (pin "19") (pinfunction "CBUS3_19") (pintype "bidirectional"))
    )
    (net (code "70") (name "Net-(U1-USBDM)") (class "Default")
      (node (ref "R3") (pin "1") (pinfunction "1_1") (pintype "passive"))
      (node (ref "U1") (pin "12") (pinfunction "USBDM_12") (pintype "bidirectional"))
    )
    (net (code "71") (name "Net-(U1-USBDP)") (class "Default")
      (node (ref "R4") (pin "1") (pinfunction "1_1") (pintype "passive"))
      (node (ref "U1") (pin "11") (pinfunction "USBDP_11") (pintype "bidirectional"))
    )
    (net (code "72") (name "Net-(U1-~{DTR})") (class "Default")
      (node (ref "C1") (pin "1") (pinfunction "1_1") (pintype "passive"))
      (node (ref "JP11") (pin "2") (pinfunction "2_2") (pintype "passive"))
      (node (ref "U1") (pin "1") (pinfunction "~{DTR}_1") (pintype "bidirectional"))
    )
    (net (code "73") (name "Net-(U3-PB3(MOSI{slash}OC2))") (class "Default")
      (node (ref "J1") (pin "4") (pinfunction "4_4") (pintype "passive"))
      (node (ref "U3") (pin "15") (pinfunction "PB3(MOSI/OC2)_15") (pintype "bidirectional"))
    )
    (net (code "74") (name "Net-(U3-PB4(MISO))") (class "Default")
      (node (ref "J1") (pin "1") (pinfunction "1_1") (pintype "passive"))
      (node (ref "U3") (pin "16") (pinfunction "PB4(MISO)_16") (pintype "bidirectional"))
    )
    (net (code "75") (name "Net-(U3-PB5(SCK))") (class "Default")
      (node (ref "J1") (pin "3") (pinfunction "3_3") (pintype "passive"))
      (node (ref "U3") (pin "17") (pinfunction "PB5(SCK)_17") (pintype "bidirectional"))
    )
    (net (code "76") (name "Net-(U3-PC0(ADC0))") (class "Default")
      (node (ref "R30") (pin "2") (pinfunction "2_2") (pintype "passive"))
      (node (ref "U3") (pin "23") (pinfunction "PC0(ADC0)_23") (pintype "bidirectional"))
    )
    (net (code "77") (name "Net-(U3-PC1(ADC1))") (class "Default")
      (node (ref "R31") (pin "2") (pinfunction "2_2") (pintype "passive"))
      (node (ref "U3") (pin "24") (pinfunction "PC1(ADC1)_24") (pintype "bidirectional"))
    )
    (net (code "78") (name "Net-(X1A-KL)") (class "Default")
      (node (ref "D1") (pin "A") (pinfunction "A_A") (pintype "passive"))
      (node (ref "X1") (pin "1") (pinfunction "KL_1") (pintype "passive"))
    )
    (net (code "79") (name "VCC") (class "Default")
      (node (ref "C12") (pin "1") (pinfunction "1_1") (pintype "passive"))
      (node (ref "C13") (pin "2") (pinfunction "2_2") (pintype "passive"))
      (node (ref "C15") (pin "2") (pinfunction "2_2") (pintype "passive"))
      (node (ref "C19") (pin "1") (pinfunction "1_1") (pintype "passive"))
      (node (ref "C2") (pin "1") (pinfunction "1_1") (pintype "passive"))
      (node (ref "C20") (pin "1") (pinfunction "1_1") (pintype "passive"))
      (node (ref "C21") (pin "1") (pinfunction "1_1") (pintype "passive"))
      (node (ref "C23") (pin "+") (pinfunction "+_+") (pintype "passive"))
      (node (ref "C3") (pin "2") (pinfunction "2_2") (pintype "passive"))
      (node (ref "C4") (pin "1") (pinfunction "1_1") (pintype "passive"))
      (node (ref "C7") (pin "1") (pinfunction "1_1") (pintype "passive"))
      (node (ref "C8") (pin "1") (pinfunction "1_1") (pintype "passive"))
      (node (ref "D2") (pin "A") (pinfunction "A_A") (pintype "passive"))
      (node (ref "IC2") (pin "8") (pinfunction "VCC_8") (pintype "power_in"))
      (node (ref "IC3") (pin "3") (pinfunction "VO_3") (pintype "passive"))
      (node (ref "IC4") (pin "16") (pinfunction "VDD_16") (pintype "power_in"))
      (node (ref "J1") (pin "2") (pinfunction "2_2") (pintype "passive"))
      (node (ref "JP5") (pin "2") (pinfunction "2_2") (pintype "passive"))
      (node (ref "JP7") (pin "1") (pinfunction "1_1") (pintype "passive"))
      (node (ref "JP8") (pin "1") (pinfunction "1_1") (pintype "passive"))
      (node (ref "Q2") (pin "2") (pinfunction "E_2") (pintype "passive"))
      (node (ref "R1") (pin "1") (pinfunction "1_1") (pintype "passive"))
      (node (ref "R11") (pin "2") (pinfunction "2_2") (pintype "passive"))
      (node (ref "R12") (pin "2") (pinfunction "2_2") (pintype "passive"))
      (node (ref "R13") (pin "2") (pinfunction "2_2") (pintype "passive"))
      (node (ref "R16") (pin "1") (pinfunction "1_1") (pintype "passive"))
      (node (ref "R17") (pin "1") (pinfunction "1_1") (pintype "passive"))
      (node (ref "R2") (pin "1") (pinfunction "1_1") (pintype "passive"))
      (node (ref "R24") (pin "2") (pinfunction "2_2") (pintype "passive"))
      (node (ref "R25") (pin "2") (pinfunction "2_2") (pintype "passive"))
      (node (ref "R28") (pin "2") (pinfunction "2_2") (pintype "passive"))
      (node (ref "R29") (pin "2") (pinfunction "2_2") (pintype "passive"))
      (node (ref "R7") (pin "1") (pinfunction "E_1") (pintype "passive"))
      (node (ref "R8") (pin "1") (pinfunction "1_1") (pintype "passive"))
      (node (ref "U1") (pin "15") (pinfunction "VCC_15") (pintype "bidirectional"))
      (node (ref "U3") (pin "18") (pinfunction "AVCC_18") (pintype "bidirectional"))
      (node (ref "U3") (pin "20") (pinfunction "AREF_20") (pintype "bidirectional"))
      (node (ref "U3") (pin "4") (pinfunction "VCC_4") (pintype "bidirectional"))
      (node (ref "U3") (pin "6") (pinfunction "VCC_6") (pintype "bidirectional"))
      (node (ref "U4") (pin "8") (pinfunction "VCC_8") (pintype "power_in"))
    )
    (net (code "80") (name "unconnected-(IC4-~{INT}-Pad13)") (class "Default")
      (node (ref "IC4") (pin "13") (pinfunction "~{INT}_13") (pintype "output"))
    )
    (net (code "81") (name "unconnected-(JP5-Pad7)") (class "Default")
      (node (ref "JP5") (pin "7") (pinfunction "7_7") (pintype "passive"))
    )
    (net (code "82") (name "unconnected-(JP5-Pad8)") (class "Default")
      (node (ref "JP5") (pin "8") (pinfunction "8_8") (pintype "passive"))
    )
    (net (code "83") (name "unconnected-(JP5-Pad9)") (class "Default")
      (node (ref "JP5") (pin "9") (pinfunction "9_9") (pintype "passive"))
    )
    (net (code "84") (name "unconnected-(JP5-Pad10)") (class "Default")
      (node (ref "JP5") (pin "10") (pinfunction "10_10") (pintype "passive"))
    )
    (net (code "85") (name "unconnected-(U1-CBUS2-Pad10)") (class "Default")
      (node (ref "U1") (pin "10") (pinfunction "CBUS2_10") (pintype "bidirectional"))
    )
    (net (code "86") (name "unconnected-(U1-~{CTS}-Pad9)") (class "Default")
      (node (ref "U1") (pin "9") (pinfunction "~{CTS}_9") (pintype "bidirectional"))
    )
    (net (code "87") (name "unconnected-(U1-~{DCD}-Pad8)") (class "Default")
      (node (ref "U1") (pin "8") (pinfunction "~{DCD}_8") (pintype "bidirectional"))
    )
    (net (code "88") (name "unconnected-(U1-~{DSR}-Pad7)") (class "Default")
      (node (ref "U1") (pin "7") (pinfunction "~{DSR}_7") (pintype "bidirectional"))
    )
    (net (code "89") (name "unconnected-(U1-~{RI}-Pad5)") (class "Default")
      (node (ref "U1") (pin "5") (pinfunction "~{RI}_5") (pintype "bidirectional"))
    )
    (net (code "90") (name "unconnected-(U1-~{RTS}-Pad2)") (class "Default")
      (node (ref "U1") (pin "2") (pinfunction "~{RTS}_2") (pintype "bidirectional"))
    )
    (net (code "91") (name "unconnected-(U3-ADC6-Pad19)") (class "Default")
      (node (ref "U3") (pin "19") (pinfunction "ADC6_19") (pintype "bidirectional"))
    )
    (net (code "92") (name "unconnected-(U3-ADC7-Pad22)") (class "Default")
      (node (ref "U3") (pin "22") (pinfunction "ADC7_22") (pintype "bidirectional"))
    )
    (net (code "93") (name "unconnected-(U4-NC-Pad5)") (class "Default")
      (node (ref "U4") (pin "5") (pinfunction "NC_5") (pintype "no_connect"))
    )
    (net (code "94") (name "unconnected-(U4-NC_2-Pad1)") (class "Default")
      (node (ref "U4") (pin "1") (pinfunction "NC_2_1") (pintype "no_connect"))
    )
  )
)
